# 3v3converter.net
KiCad netlist of a schematic drawn in EAGLE
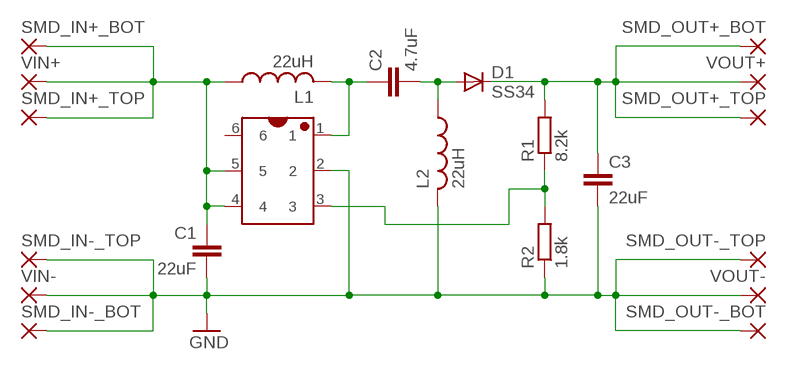
[diagram p0: schematic, sheet 1]

(export (version "E")
  (design (tool "Eeschema 10.0.6"))
  (components
    (comp (ref "C1")
      (value "22uF")
      (footprint "eagle-import:C0805")
      (libsource (lib "eagle-import") (part "C-EUC0805"))
    )
    (comp (ref "C2")
      (value "4.7uF")
      (footprint "eagle-import:C0603")
      (libsource (lib "eagle-import") (part "C-EUC0603"))
    )
    (comp (ref "C3")
      (value "22uF")
      (footprint "eagle-import:C0805")
      (libsource (lib "eagle-import") (part "C-EUC0805"))
    )
    (comp (ref "D1")
      (value "SS34")
      (footprint "eagle-import:DO214BA")
      (libsource (lib "eagle-import") (part "DIODE-DO214BA"))
    )
    (comp (ref "L1")
      (value "22uH")
      (footprint "eagle-import:FPS")
      (libsource (lib "eagle-import") (part "L-USFPS"))
    )
    (comp (ref "L2")
      (value "22uH")
      (footprint "eagle-import:FPS")
      (libsource (lib "eagle-import") (part "L-USFPS"))
    )
    (comp (ref "MT3608")
      (value "mt3608")
      (footprint "eagle-import:SOT-23-6")
      (libsource (lib "eagle-import") (part "SOT-23-6"))
    )
    (comp (ref "R1")
      (value "8.2k")
      (footprint "eagle-import:R0603")
      (libsource (lib "eagle-import") (part "R-EU_R0603"))
    )
    (comp (ref "R2")
      (value "1.8k")
      (footprint "eagle-import:R0603")
      (libsource (lib "eagle-import") (part "R-EU_R0603"))
    )
    (comp (ref "SMD_IN+_BOT")
      (value "SMD5")
      (footprint "eagle-import:SMD2,54-5,08")
      (libsource (lib "eagle-import") (part "SMD5"))
    )
    (comp (ref "SMD_IN+_TOP")
      (value "SMD5")
      (footprint "eagle-import:SMD2,54-5,08")
      (libsource (lib "eagle-import") (part "SMD5"))
    )
    (comp (ref "SMD_IN-_BOT")
      (value "SMD5")
      (footprint "eagle-import:SMD2,54-5,08")
      (libsource (lib "eagle-import") (part "SMD5"))
    )
    (comp (ref "SMD_IN-_TOP")
      (value "SMD5")
      (footprint "eagle-import:SMD2,54-5,08")
      (libsource (lib "eagle-import") (part "SMD5"))
    )
    (comp (ref "SMD_OUT+_BOT")
      (value "SMD5")
      (footprint "eagle-import:SMD2,54-5,08")
      (libsource (lib "eagle-import") (part "SMD5"))
    )
    (comp (ref "SMD_OUT+_TOP")
      (value "SMD5")
      (footprint "eagle-import:SMD2,54-5,08")
      (libsource (lib "eagle-import") (part "SMD5"))
    )
    (comp (ref "SMD_OUT-_BOT")
      (value "SMD5")
      (footprint "eagle-import:SMD2,54-5,08")
      (libsource (lib "eagle-import") (part "SMD5"))
    )
    (comp (ref "SMD_OUT-_TOP")
      (value "SMD5")
      (footprint "eagle-import:SMD2,54-5,08")
      (libsource (lib "eagle-import") (part "SMD5"))
    )
    (comp (ref "VIN+")
      (value "1,6/0,9")
      (footprint "eagle-import:1,6_0,9")
      (libsource (lib "eagle-import") (part "1,6/0,9"))
    )
    (comp (ref "VIN-")
      (value "1,6/0,9")
      (footprint "eagle-import:1,6_0,9")
      (libsource (lib "eagle-import") (part "1,6/0,9"))
    )
    (comp (ref "VOUT+")
      (value "1,6/0,9")
      (footprint "eagle-import:1,6_0,9")
      (libsource (lib "eagle-import") (part "1,6/0,9"))
    )
    (comp (ref "VOUT-")
      (value "1,6/0,9")
      (footprint "eagle-import:1,6_0,9")
      (libsource (lib "eagle-import") (part "1,6/0,9"))
    )
  )
  (nets
    (net (code "1") (name "GND") (class "Default")
      (node (ref "C1") (pin "2") (pinfunction "2_2") (pintype "passive"))
      (node (ref "C3") (pin "2") (pinfunction "2_2") (pintype "passive"))
      (node (ref "L2") (pin "P$2") (pinfunction "2_P$2") (pintype "passive"))
      (node (ref "MT3608") (pin "2") (pinfunction "2_2") (pintype "bidirectional"))
      (node (ref "R2") (pin "1") (pinfunction "1_1") (pintype "passive"))
      (node (ref "SMD_IN-_BOT") (pin "1") (pinfunction "P_1") (pintype "passive"))
      (node (ref "SMD_IN-_TOP") (pin "1") (pinfunction "P_1") (pintype "passive"))
      (node (ref "SMD_OUT-_BOT") (pin "1") (pinfunction "P_1") (pintype "passive"))
      (node (ref "SMD_OUT-_TOP") (pin "1") (pinfunction "P_1") (pintype "passive"))
      (node (ref "VIN-") (pin "1") (pinfunction "P_1") (pintype "passive"))
      (node (ref "VOUT-") (pin "1") (pinfunction "P_1") (pintype "passive"))
    )
    (net (code "2") (name "Net-(L1-1)") (class "Default")
      (node (ref "C1") (pin "1") (pinfunction "1_1") (pintype "passive"))
      (node (ref "L1") (pin "P$1") (pinfunction "1_P$1") (pintype "passive"))
      (node (ref "MT3608") (pin "4") (pinfunction "4_4") (pintype "bidirectional"))
      (node (ref "MT3608") (pin "5") (pinfunction "5_5") (pintype "bidirectional"))
      (node (ref "SMD_IN+_BOT") (pin "1") (pinfunction "P_1") (pintype "passive"))
      (node (ref "SMD_IN+_TOP") (pin "1") (pinfunction "P_1") (pintype "passive"))
      (node (ref "VIN+") (pin "1") (pinfunction "P_1") (pintype "passive"))
    )
    (net (code "3") (name "Net-(L1-2)") (class "Default")
      (node (ref "C2") (pin "1") (pinfunction "1_1") (pintype "passive"))
      (node (ref "L1") (pin "P$2") (pinfunction "2_P$2") (pintype "passive"))
      (node (ref "MT3608") (pin "1") (pinfunction "1_1") (pintype "bidirectional"))
    )
    (net (code "4") (name "Net-(L2-1)") (class "Default")
      (node (ref "C2") (pin "2") (pinfunction "2_2") (pintype "passive"))
      (node (ref "D1") (pin "A") (pinfunction "A_A") (pintype "passive"))
      (node (ref "L2") (pin "P$1") (pinfunction "1_P$1") (pintype "passive"))
    )
    (net (code "5") (name "Net-(MT3608-Pad3)") (class "Default")
      (node (ref "MT3608") (pin "3") (pinfunction "3_3") (pintype "bidirectional"))
      (node (ref "R1") (pin "1") (pinfunction "1_1") (pintype "passive"))
      (node (ref "R2") (pin "2") (pinfunction "2_2") (pintype "passive"))
    )
    (net (code "6") (name "Net-(SMD_OUT+_BOT-P)") (class "Default")
      (node (ref "C3") (pin "1") (pinfunction "1_1") (pintype "passive"))
      (node (ref "D1") (pin "C") (pinfunction "C_C") (pintype "passive"))
      (node (ref "R1") (pin "2") (pinfunction "2_2") (pintype "passive"))
      (node (ref "SMD_OUT+_BOT") (pin "1") (pinfunction "P_1") (pintype "passive"))
      (node (ref "SMD_OUT+_TOP") (pin "1") (pinfunction "P_1") (pintype "passive"))
      (node (ref "VOUT+") (pin "1") (pinfunction "P_1") (pintype "passive"))
    )
    (net (code "7") (name "unconnected-(MT3608-Pad6)") (class "Default")
      (node (ref "MT3608") (pin "6") (pinfunction "6_6") (pintype "bidirectional"))
    )
  )
)
